# OpenMPPT2-Safety.net
KiCad netlist of a schematic drawn in Altium Designer
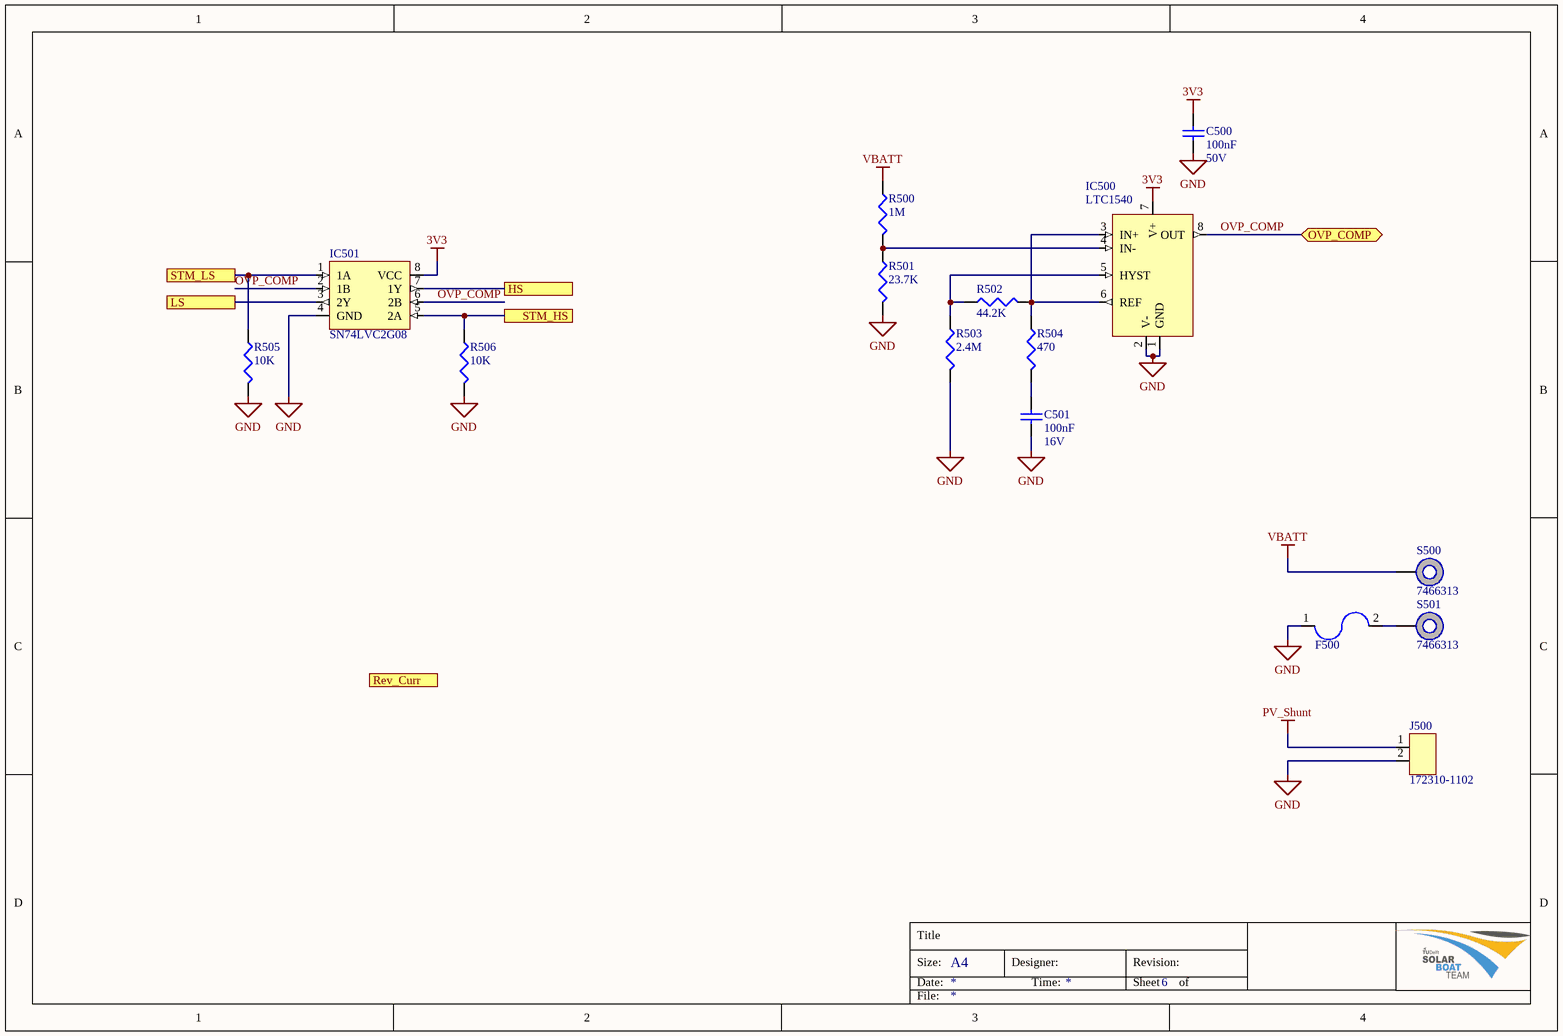
[diagram p0: OpenMPPT2-Safety.SchDoc]

(export (version "E")
  (design (tool "Eeschema 10.0.6"))
  (components
    (comp (ref "C500")
      (value "100nF")
      (footprint "C0603")
      (description "Capacitor, 100nF, 50V, X7R")
      (fields (field (name "VOLTAGE RATING") "50V"))
      (libsource (lib "SBT_Capacitors_Ceramic") (part "100nF/0603/CER/50V"))
    )
    (comp (ref "C501")
      (value "100nF")
      (footprint "C0603")
      (description "Capacitor, 100nF, 16V, X7R")
      (fields (field (name "VOLTAGE RATING") "16V"))
      (libsource (lib "SBT_Capacitors_Ceramic") (part "100nF/0603/CER/16V"))
    )
    (comp (ref "F500")
      (value "0154010.DR")
      (footprint "0154010.DR")
      (description "Miniature SMD Fuse and Holder Assembly, 10A")
      (libsource (lib "SBT_DannyLib") (part "0154010.DR"))
    )
    (comp (ref "IC500")
      (value "LTC1540")
      (footprint "SO-8")
      (description "ANALOGUE COMPARATOR, RAIL TO RAIL")
      (libsource (lib "SBT_ICs") (part "LTC1540"))
    )
    (comp (ref "IC501")
      (value "SN74LVC2G08")
      (footprint "SSOP-8")
      (description "Dual 2-Input Positive-AND Gate")
      (libsource (lib "SBT_ICs") (part "SN74LVC2G08"))
    )
    (comp (ref "J500")
      (value "172310-1102")
      (footprint "Ultra Fit 2P - Right Angle")
      (description "Molex ultra-fit 2 pins connector, single row, right angle")
      (libsource (lib "SBT_Connectors") (part "172310-1102"))
    )
    (comp (ref "R500")
      (value "1M")
      (footprint "0603")
      (description "Resistor, 1M, 1%, 0.063W, 50V, 100PPM, 0603")
      (libsource (lib "SBT_Resistors_SMD") (part "1M/0603/0063W/50V"))
    )
    (comp (ref "R501")
      (value "23.7K")
      (footprint "0603")
      (description "Resistor, 23.7K, 1%, 0.1W, 75V, 100PPM, 0603")
      (libsource (lib "SBT_Resistors_SMD") (part "23.7K/0603/0100W/75V"))
    )
    (comp (ref "R502")
      (value "44.2K")
      (footprint "0603")
      (description "Resistor, 44.2K, 1%, 0.1W, 75V, 100PPM, 0603")
      (libsource (lib "SBT_Resistors_SMD") (part "44.2K/0603/0100W/75V"))
    )
    (comp (ref "R503")
      (value "2.4M")
      (footprint "0603")
      (description "Resistor, 2.4M, 1%, 0.1W, 75V, 100PPM, 0603")
      (libsource (lib "SBT_Resistors_SMD") (part "2.4M/0603/0100W/75V"))
    )
    (comp (ref "R504")
      (value "470")
      (footprint "0603")
      (description "Resistor, 470, 1%, 0.063W, 50V, 100PPM, 0603")
      (libsource (lib "SBT_Resistors_SMD") (part "470/0603/0063W/50V"))
    )
    (comp (ref "R505")
      (value "10K")
      (footprint "0603")
      (description "Resistor, 10K, 1%, 0.063W, 50V, 100PPM, 0603")
      (libsource (lib "SBT_Resistors_SMD") (part "10K/0603/0063W/50V"))
    )
    (comp (ref "R506")
      (value "10K")
      (footprint "0603")
      (description "Resistor, 10K, 1%, 0.063W, 50V, 100PPM, 0603")
      (libsource (lib "SBT_Resistors_SMD") (part "10K/0603/0063W/50V"))
    )
    (comp (ref "S500")
      (value "7466313")
      (footprint "7466313")
      (description "WP-SMRA SMT Right Angle M3 Thread")
      (fields (field (name "PUBLISHER") "Wurth Elektronik"))
      (libsource (lib "ALTIUM-SMD_RIGHT_ANGLED-rev16a") (part "7466313"))
    )
    (comp (ref "S501")
      (value "7466313")
      (footprint "7466313")
      (description "WP-SMRA SMT Right Angle M3 Thread")
      (fields (field (name "PUBLISHER") "Wurth Elektronik"))
      (libsource (lib "ALTIUM-SMD_RIGHT_ANGLED-rev16a") (part "7466313"))
    )
  )
  (nets
    (net (code "1") (name "/HS") (class "Default")
      (node (ref "IC501") (pin "7") (pinfunction "1Y_7") (pintype "output"))
    )
    (net (code "2") (name "/LS") (class "Default")
      (node (ref "IC501") (pin "3") (pinfunction "2Y_3") (pintype "output"))
    )
    (net (code "3") (name "/OVP_COMP") (class "Default")
      (node (ref "IC500") (pin "8") (pinfunction "OUT_8") (pintype "output"))
      (node (ref "IC501") (pin "2") (pinfunction "1B_2") (pintype "input"))
      (node (ref "IC501") (pin "6") (pinfunction "2B_6") (pintype "input"))
    )
    (net (code "5") (name "/STM_HS") (class "Default")
      (node (ref "IC501") (pin "5") (pinfunction "2A_5") (pintype "input"))
      (node (ref "R506") (pin "1") (pinfunction "1_1") (pintype "passive"))
    )
    (net (code "6") (name "/STM_LS") (class "Default")
      (node (ref "IC501") (pin "1") (pinfunction "1A_1") (pintype "input"))
      (node (ref "R505") (pin "1") (pinfunction "1_1") (pintype "passive"))
    )
    (net (code "7") (name "3V3") (class "Default")
      (node (ref "C500") (pin "2") (pinfunction "2_2") (pintype "passive"))
      (node (ref "IC500") (pin "7") (pinfunction "V+_7") (pintype "power_in"))
      (node (ref "IC501") (pin "8") (pinfunction "VCC_8") (pintype "power_in"))
    )
    (net (code "8") (name "GND") (class "Default")
      (node (ref "C500") (pin "1") (pinfunction "1_1") (pintype "passive"))
      (node (ref "C501") (pin "2") (pinfunction "2_2") (pintype "passive"))
      (node (ref "F500") (pin "1") (pinfunction "1_1") (pintype "passive"))
      (node (ref "IC500") (pin "1") (pinfunction "GND_1") (pintype "power_in"))
      (node (ref "IC500") (pin "2") (pinfunction "V-_2") (pintype "power_in"))
      (node (ref "IC501") (pin "4") (pinfunction "GND_4") (pintype "power_in"))
      (node (ref "J500") (pin "2") (pinfunction "2_2") (pintype "passive"))
      (node (ref "R501") (pin "2") (pinfunction "2_2") (pintype "passive"))
      (node (ref "R503") (pin "2") (pinfunction "2_2") (pintype "passive"))
      (node (ref "R505") (pin "2") (pinfunction "2_2") (pintype "passive"))
      (node (ref "R506") (pin "2") (pinfunction "2_2") (pintype "passive"))
    )
    (net (code "9") (name "Net-(C501-Pad1)") (class "Default")
      (node (ref "C501") (pin "1") (pinfunction "1_1") (pintype "passive"))
      (node (ref "R504") (pin "2") (pinfunction "2_2") (pintype "passive"))
    )
    (net (code "10") (name "Net-(F500-Pad2)") (class "Default")
      (node (ref "F500") (pin "2") (pinfunction "2_2") (pintype "passive"))
      (node (ref "S501") (pin "1") (pinfunction "1_1") (pintype "passive"))
    )
    (net (code "11") (name "Net-(IC500-HYST)") (class "Default")
      (node (ref "IC500") (pin "5") (pinfunction "HYST_5") (pintype "input"))
      (node (ref "R502") (pin "1") (pinfunction "1_1") (pintype "passive"))
      (node (ref "R503") (pin "1") (pinfunction "1_1") (pintype "passive"))
    )
    (net (code "12") (name "Net-(IC500-IN+)") (class "Default")
      (node (ref "IC500") (pin "3") (pinfunction "IN+_3") (pintype "input"))
      (node (ref "IC500") (pin "6") (pinfunction "REF_6") (pintype "output"))
      (node (ref "R502") (pin "2") (pinfunction "2_2") (pintype "passive"))
      (node (ref "R504") (pin "1") (pinfunction "1_1") (pintype "passive"))
    )
    (net (code "13") (name "Net-(IC500-IN-)") (class "Default")
      (node (ref "IC500") (pin "4") (pinfunction "IN-_4") (pintype "input"))
      (node (ref "R500") (pin "2") (pinfunction "2_2") (pintype "passive"))
      (node (ref "R501") (pin "1") (pinfunction "1_1") (pintype "passive"))
    )
    (net (code "14") (name "PV_Shunt") (class "Default")
      (node (ref "J500") (pin "1") (pinfunction "1_1") (pintype "passive"))
    )
    (net (code "15") (name "VBATT") (class "Default")
      (node (ref "R500") (pin "1") (pinfunction "1_1") (pintype "passive"))
      (node (ref "S500") (pin "1") (pinfunction "1_1") (pintype "passive"))
    )
  )
)
